# 08_BB_Processor.net
KiCad netlist of a schematic drawn in Altium Designer
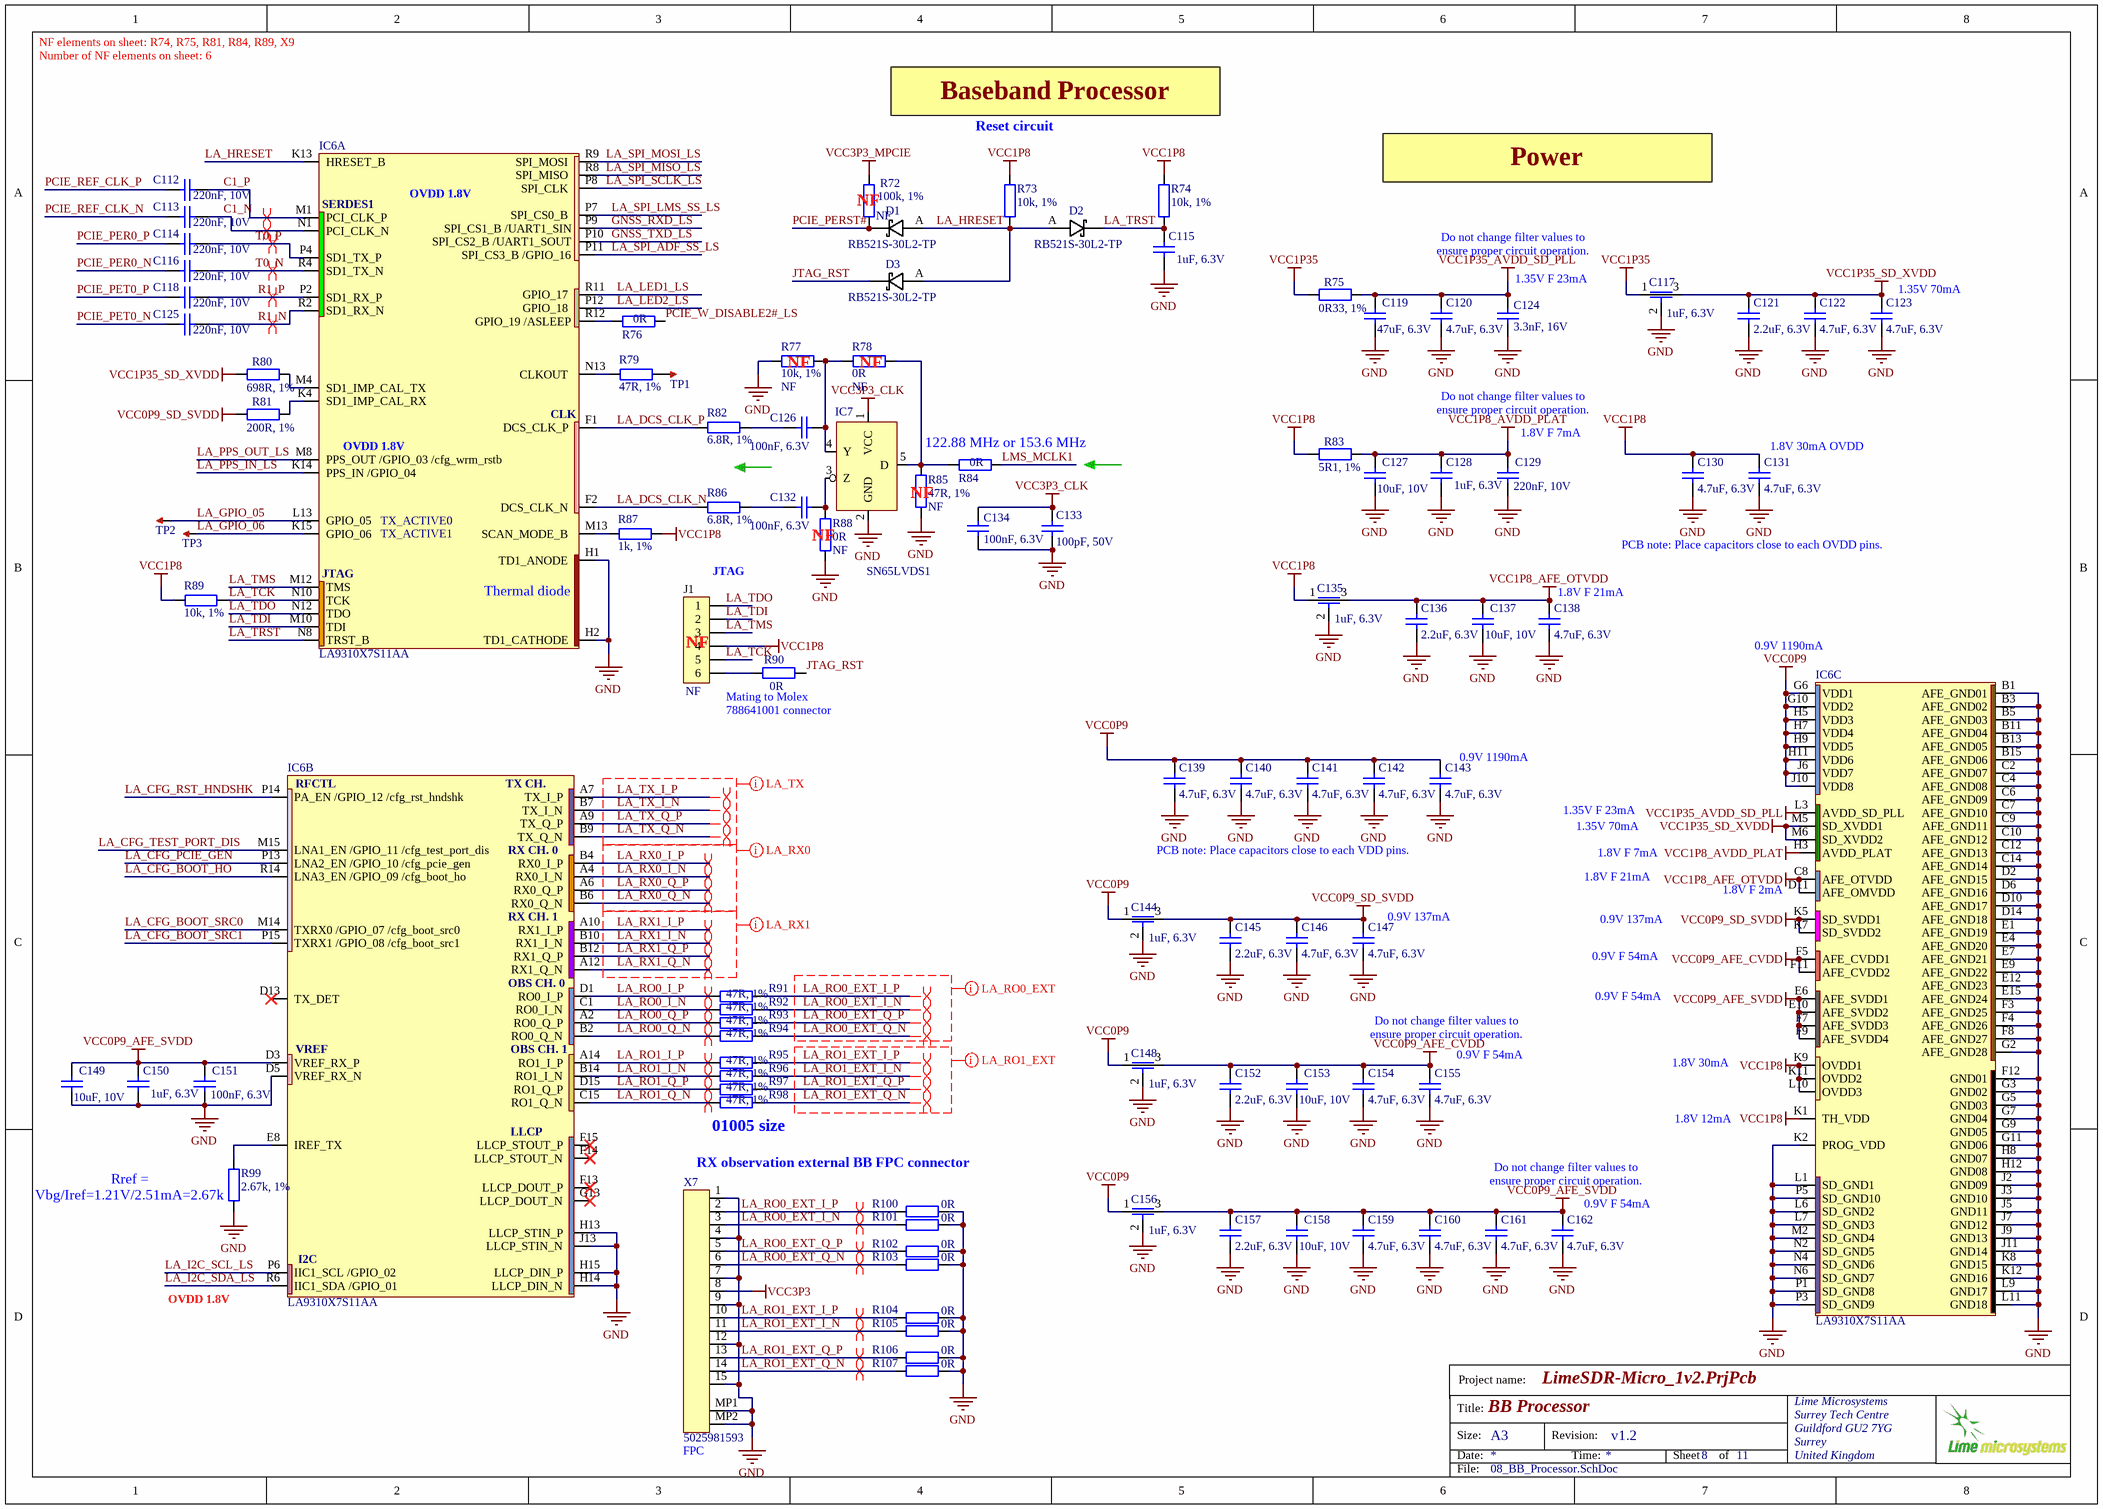
[diagram p0: 08_BB_Processor.SchDoc]

(export (version "E")
  (design (tool "Eeschema 10.0.6"))
  (components
    (comp (ref "C112")
      (value "220nF, 10V")
      (footprint "CAP0201")
      (fields
        (field (name "MANUFACTURER") "Murata")
        (field (name "TOLERANCE") "20%")
        (field (name "VOLTAGE") "10V")
      )
      (libsource (lib "LimeMicroAltiumLib_schLib") (part "Cap_0402"))
    )
    (comp (ref "C113")
      (value "220nF, 10V")
      (footprint "CAP0201")
      (fields
        (field (name "MANUFACTURER") "Murata")
        (field (name "TOLERANCE") "20%")
        (field (name "VOLTAGE") "10V")
      )
      (libsource (lib "LimeMicroAltiumLib_schLib") (part "Cap_0402"))
    )
    (comp (ref "C114")
      (value "220nF, 10V")
      (footprint "CAP0201")
      (fields
        (field (name "MANUFACTURER") "Murata")
        (field (name "TOLERANCE") "20%")
        (field (name "VOLTAGE") "10V")
      )
      (libsource (lib "LimeMicroAltiumLib_schLib") (part "Cap_0402"))
    )
    (comp (ref "C115")
      (value "1uF, 6.3V")
      (footprint "CAP0201")
      (fields (field (name "TOLERANCE") "±20%") (field (name "MANUFACTURER") "TDK Corporation"))
      (libsource (lib "LimeMicroAltiumLib_schLib") (part "Cap_0402"))
    )
    (comp (ref "C116")
      (value "220nF, 10V")
      (footprint "CAP0201")
      (fields
        (field (name "MANUFACTURER") "Murata")
        (field (name "TOLERANCE") "20%")
        (field (name "VOLTAGE") "10V")
      )
      (libsource (lib "LimeMicroAltiumLib_schLib") (part "Cap_0402"))
    )
    (comp (ref "C117")
      (value "1uF, 6.3V")
      (footprint "CAP0603_FEEDTHROUGH")
      (fields (field (name "MANUFACTURER") "TDK"))
      (libsource (lib "LimeMicroAltiumLib_schLib_r01") (part "Cap_feed_through"))
    )
    (comp (ref "C118")
      (value "220nF, 10V")
      (footprint "CAP0201")
      (fields
        (field (name "MANUFACTURER") "Murata")
        (field (name "TOLERANCE") "20%")
        (field (name "VOLTAGE") "10V")
      )
      (libsource (lib "LimeMicroAltiumLib_schLib") (part "Cap_0402"))
    )
    (comp (ref "C119")
      (value "47uF, 6.3V")
      (footprint "CAP0603")
      (fields (field (name "MANUFACTURER") "Murata") (field (name "TOLERANCE") "20%"))
      (libsource (lib "LimeFPGAboard_schLib") (part "Cap_0603"))
    )
    (comp (ref "C120")
      (value "4.7uF, 6.3V")
      (footprint "CAP0201")
      (fields (field (name "MANUFACTURER") "Murata") (field (name "TOLERANCE") "20%"))
      (libsource (lib "LimeMicroAltiumLib_schLib") (part "Cap_0402"))
    )
    (comp (ref "C121")
      (value "2.2uF, 6.3V")
      (footprint "CAP0201")
      (fields (field (name "MANUFACTURER") "Murata") (field (name "TOLERANCE") "20%"))
      (libsource (lib "LimeMicroAltiumLib_schLib") (part "Cap_0402"))
    )
    (comp (ref "C122")
      (value "4.7uF, 6.3V")
      (footprint "CAP0201")
      (fields (field (name "MANUFACTURER") "Murata") (field (name "TOLERANCE") "20%"))
      (libsource (lib "LimeMicroAltiumLib_schLib") (part "Cap_0402"))
    )
    (comp (ref "C123")
      (value "4.7uF, 6.3V")
      (footprint "CAP0201")
      (fields (field (name "MANUFACTURER") "Murata") (field (name "TOLERANCE") "20%"))
      (libsource (lib "LimeMicroAltiumLib_schLib") (part "Cap_0402"))
    )
    (comp (ref "C124")
      (value "3.3nF, 16V")
      (footprint "CAP0201")
      (fields (field (name "MANUFACTURER") "Murata"))
      (libsource (lib "LimeMicroAltiumLib_schLib") (part "Cap_0402"))
    )
    (comp (ref "C125")
      (value "220nF, 10V")
      (footprint "CAP0201")
      (fields
        (field (name "MANUFACTURER") "Murata")
        (field (name "TOLERANCE") "20%")
        (field (name "VOLTAGE") "10V")
      )
      (libsource (lib "LimeMicroAltiumLib_schLib") (part "Cap_0402"))
    )
    (comp (ref "C126")
      (value "100nF, 6.3V")
      (footprint "CAP0201")
      (fields (field (name "MANUFACTURER") "Samsung") (field (name "TOLERANCE") "20%"))
      (libsource (lib "LimeMicroAltiumLib_schLib") (part "Cap_0402"))
    )
    (comp (ref "C127")
      (value "10uF, 10V")
      (footprint "CAP0402")
      (fields (field (name "MANUFACTURER") "Murata"))
      (libsource (lib "LimeFPGAboard_schLib") (part "Cap_0603"))
    )
    (comp (ref "C128")
      (value "1uF, 6.3V")
      (footprint "CAP0201")
      (fields (field (name "TOLERANCE") "±20%") (field (name "MANUFACTURER") "TDK Corporation"))
      (libsource (lib "LimeMicroAltiumLib_schLib") (part "Cap_0402"))
    )
    (comp (ref "C129")
      (value "220nF, 10V")
      (footprint "CAP0201")
      (fields
        (field (name "MANUFACTURER") "Murata")
        (field (name "TOLERANCE") "20%")
        (field (name "VOLTAGE") "10V")
      )
      (libsource (lib "LimeMicroAltiumLib_schLib") (part "Cap_0402"))
    )
    (comp (ref "C130")
      (value "4.7uF, 6.3V")
      (footprint "CAP0201")
      (fields (field (name "MANUFACTURER") "Murata") (field (name "TOLERANCE") "20%"))
      (libsource (lib "LimeMicroAltiumLib_schLib") (part "Cap_0402"))
    )
    (comp (ref "C131")
      (value "4.7uF, 6.3V")
      (footprint "CAP0201")
      (fields (field (name "MANUFACTURER") "Murata") (field (name "TOLERANCE") "20%"))
      (libsource (lib "LimeMicroAltiumLib_schLib") (part "Cap_0402"))
    )
    (comp (ref "C132")
      (value "100nF, 6.3V")
      (footprint "CAP0201")
      (fields (field (name "MANUFACTURER") "Samsung") (field (name "TOLERANCE") "20%"))
      (libsource (lib "LimeMicroAltiumLib_schLib") (part "Cap_0402"))
    )
    (comp (ref "C133")
      (value "100pF, 50V")
      (footprint "CAP0201")
      (fields
        (field (name "MANUFACTURER") "TDK")
        (field (name "TOLERANCE") "5%")
        (field (name "VOLTAGE") "50V")
      )
      (libsource (lib "LimeMicroAltiumLib_schLib") (part "Cap_0402"))
    )
    (comp (ref "C134")
      (value "100nF, 6.3V")
      (footprint "CAP0201")
      (fields (field (name "MANUFACTURER") "Samsung") (field (name "TOLERANCE") "20%"))
      (libsource (lib "LimeMicroAltiumLib_schLib") (part "Cap_0402"))
    )
    (comp (ref "C135")
      (value "1uF, 6.3V")
      (footprint "CAP0603_FEEDTHROUGH")
      (fields (field (name "MANUFACTURER") "TDK"))
      (libsource (lib "LimeMicroAltiumLib_schLib_r01") (part "Cap_feed_through"))
    )
    (comp (ref "C136")
      (value "2.2uF, 6.3V")
      (footprint "CAP0201")
      (fields (field (name "MANUFACTURER") "Murata") (field (name "TOLERANCE") "20%"))
      (libsource (lib "LimeMicroAltiumLib_schLib") (part "Cap_0402"))
    )
    (comp (ref "C137")
      (value "10uF, 10V")
      (footprint "CAP0402")
      (fields (field (name "MANUFACTURER") "Murata"))
      (libsource (lib "LimeFPGAboard_schLib") (part "Cap_0603"))
    )
    (comp (ref "C138")
      (value "4.7uF, 6.3V")
      (footprint "CAP0201")
      (fields (field (name "MANUFACTURER") "Murata") (field (name "TOLERANCE") "20%"))
      (libsource (lib "LimeMicroAltiumLib_schLib") (part "Cap_0402"))
    )
    (comp (ref "C139")
      (value "4.7uF, 6.3V")
      (footprint "CAP0201")
      (fields (field (name "MANUFACTURER") "Murata") (field (name "TOLERANCE") "20%"))
      (libsource (lib "LimeMicroAltiumLib_schLib") (part "Cap_0402"))
    )
    (comp (ref "C140")
      (value "4.7uF, 6.3V")
      (footprint "CAP0201")
      (fields (field (name "MANUFACTURER") "Murata") (field (name "TOLERANCE") "20%"))
      (libsource (lib "LimeMicroAltiumLib_schLib") (part "Cap_0402"))
    )
    (comp (ref "C141")
      (value "4.7uF, 6.3V")
      (footprint "CAP0201")
      (fields (field (name "MANUFACTURER") "Murata") (field (name "TOLERANCE") "20%"))
      (libsource (lib "LimeMicroAltiumLib_schLib") (part "Cap_0402"))
    )
    (comp (ref "C142")
      (value "4.7uF, 6.3V")
      (footprint "CAP0201")
      (fields (field (name "MANUFACTURER") "Murata") (field (name "TOLERANCE") "20%"))
      (libsource (lib "LimeMicroAltiumLib_schLib") (part "Cap_0402"))
    )
    (comp (ref "C143")
      (value "4.7uF, 6.3V")
      (footprint "CAP0201")
      (fields (field (name "MANUFACTURER") "Murata") (field (name "TOLERANCE") "20%"))
      (libsource (lib "LimeMicroAltiumLib_schLib") (part "Cap_0402"))
    )
    (comp (ref "C144")
      (value "1uF, 6.3V")
      (footprint "CAP0603_FEEDTHROUGH")
      (fields (field (name "MANUFACTURER") "TDK"))
      (libsource (lib "LimeMicroAltiumLib_schLib_r01") (part "Cap_feed_through"))
    )
    (comp (ref "C145")
      (value "2.2uF, 6.3V")
      (footprint "CAP0201")
      (fields (field (name "MANUFACTURER") "Murata") (field (name "TOLERANCE") "20%"))
      (libsource (lib "LimeMicroAltiumLib_schLib") (part "Cap_0402"))
    )
    (comp (ref "C146")
      (value "4.7uF, 6.3V")
      (footprint "CAP0201")
      (fields (field (name "MANUFACTURER") "Murata") (field (name "TOLERANCE") "20%"))
      (libsource (lib "LimeMicroAltiumLib_schLib") (part "Cap_0402"))
    )
    (comp (ref "C147")
      (value "4.7uF, 6.3V")
      (footprint "CAP0201")
      (fields (field (name "MANUFACTURER") "Murata") (field (name "TOLERANCE") "20%"))
      (libsource (lib "LimeMicroAltiumLib_schLib") (part "Cap_0402"))
    )
    (comp (ref "C148")
      (value "1uF, 6.3V")
      (footprint "CAP0603_FEEDTHROUGH")
      (fields (field (name "MANUFACTURER") "TDK"))
      (libsource (lib "LimeMicroAltiumLib_schLib_r01") (part "Cap_feed_through"))
    )
    (comp (ref "C149")
      (value "10uF, 10V")
      (footprint "CAP0402")
      (fields (field (name "MANUFACTURER") "Murata"))
      (libsource (lib "LimeFPGAboard_schLib") (part "Cap_0603"))
    )
    (comp (ref "C150")
      (value "1uF, 6.3V")
      (footprint "CAP0201")
      (fields (field (name "TOLERANCE") "±20%") (field (name "MANUFACTURER") "TDK Corporation"))
      (libsource (lib "LimeMicroAltiumLib_schLib") (part "Cap_0402"))
    )
    (comp (ref "C151")
      (value "100nF, 6.3V")
      (footprint "CAP0201")
      (fields (field (name "MANUFACTURER") "Samsung") (field (name "TOLERANCE") "20%"))
      (libsource (lib "LimeMicroAltiumLib_schLib") (part "Cap_0402"))
    )
    (comp (ref "C152")
      (value "2.2uF, 6.3V")
      (footprint "CAP0201")
      (fields (field (name "MANUFACTURER") "Murata") (field (name "TOLERANCE") "20%"))
      (libsource (lib "LimeMicroAltiumLib_schLib") (part "Cap_0402"))
    )
    (comp (ref "C153")
      (value "10uF, 10V")
      (footprint "CAP0402")
      (fields (field (name "MANUFACTURER") "Murata"))
      (libsource (lib "LimeFPGAboard_schLib") (part "Cap_0603"))
    )
    (comp (ref "C154")
      (value "4.7uF, 6.3V")
      (footprint "CAP0201")
      (fields (field (name "MANUFACTURER") "Murata") (field (name "TOLERANCE") "20%"))
      (libsource (lib "LimeMicroAltiumLib_schLib") (part "Cap_0402"))
    )
    (comp (ref "C155")
      (value "4.7uF, 6.3V")
      (footprint "CAP0201")
      (fields (field (name "MANUFACTURER") "Murata") (field (name "TOLERANCE") "20%"))
      (libsource (lib "LimeMicroAltiumLib_schLib") (part "Cap_0402"))
    )
    (comp (ref "C156")
      (value "1uF, 6.3V")
      (footprint "CAP0603_FEEDTHROUGH")
      (fields (field (name "MANUFACTURER") "TDK"))
      (libsource (lib "LimeMicroAltiumLib_schLib_r01") (part "Cap_feed_through"))
    )
    (comp (ref "C157")
      (value "2.2uF, 6.3V")
      (footprint "CAP0201")
      (fields (field (name "MANUFACTURER") "Murata") (field (name "TOLERANCE") "20%"))
      (libsource (lib "LimeMicroAltiumLib_schLib") (part "Cap_0402"))
    )
    (comp (ref "C158")
      (value "10uF, 10V")
      (footprint "CAP0402")
      (fields (field (name "MANUFACTURER") "Murata"))
      (libsource (lib "LimeFPGAboard_schLib") (part "Cap_0603"))
    )
    (comp (ref "C159")
      (value "4.7uF, 6.3V")
      (footprint "CAP0201")
      (fields (field (name "MANUFACTURER") "Murata") (field (name "TOLERANCE") "20%"))
      (libsource (lib "LimeMicroAltiumLib_schLib") (part "Cap_0402"))
    )
    (comp (ref "C160")
      (value "4.7uF, 6.3V")
      (footprint "CAP0201")
      (fields (field (name "MANUFACTURER") "Murata") (field (name "TOLERANCE") "20%"))
      (libsource (lib "LimeMicroAltiumLib_schLib") (part "Cap_0402"))
    )
    (comp (ref "C161")
      (value "4.7uF, 6.3V")
      (footprint "CAP0201")
      (fields (field (name "MANUFACTURER") "Murata") (field (name "TOLERANCE") "20%"))
      (libsource (lib "LimeMicroAltiumLib_schLib") (part "Cap_0402"))
    )
    (comp (ref "C162")
      (value "4.7uF, 6.3V")
      (footprint "CAP0201")
      (fields (field (name "MANUFACTURER") "Murata") (field (name "TOLERANCE") "20%"))
      (libsource (lib "LimeMicroAltiumLib_schLib") (part "Cap_0402"))
    )
    (comp (ref "D1")
      (value "RB521S-30L2-TP")
      (footprint "RB521S-30L2-TP_DFN1006")
      (fields (field (name "MANUFACTURER") "MCC"))
      (libsource (lib "LimeMicroAltiumLib") (part "BAT46JFILM_shottky_diode"))
    )
    (comp (ref "D2")
      (value "RB521S-30L2-TP")
      (footprint "RB521S-30L2-TP_DFN1006")
      (fields (field (name "MANUFACTURER") "MCC"))
      (libsource (lib "LimeMicroAltiumLib") (part "BAT46JFILM_shottky_diode"))
    )
    (comp (ref "D3")
      (value "RB521S-30L2-TP")
      (footprint "RB521S-30L2-TP_DFN1006")
      (fields (field (name "MANUFACTURER") "MCC"))
      (libsource (lib "LimeMicroAltiumLib") (part "BAT46JFILM_shottky_diode"))
    )
    (comp (ref "IC6")
      (value "LA9310X7S11AA")
      (footprint "LA9310X7S11AA")
      (fields (field (name "MANUFACTURER") "NXP Semiconductors"))
      (libsource (lib "LimeMicroAltiumLib") (part "LA9310X7S11AA"))
    )
    (comp (ref "IC7")
      (value "SN65LVDS1")
      (footprint "SOT23-5_NO_SILK")
      (fields (field (name "MANUFACTURER") "TEXAS INSTRUMENTS"))
      (libsource (lib "LimeMicroAltiumLib_schLib") (part "SN65LVDS1"))
    )
    (comp (ref "J1")
      (value "Molex 0788641001")
      (footprint "Molex_0788641001_spring_contacts")
      (description "Header, 6-pin")
      (fields (field (name "MANUFACTURER") "Molex") (field (name "ASSEMBLY INFO") "NF"))
      (libsource (lib "LimeMicroAltiumLib_schLib_r04") (part "Molex_0788641001_spring_contacts"))
    )
    (comp (ref "R72")
      (value "100k, 1%")
      (footprint "RES0201")
      (fields
        (field (name "ASSEMBLY INFO") "NF")
        (field (name "MANUFACTURER") "Yageo")
        (field (name "TOLERANCE") "1%")
      )
      (libsource (lib "LimeFPGAboard_schLib") (part "Res_0402"))
    )
    (comp (ref "R73")
      (value "10k, 1%")
      (footprint "RES0201")
      (fields (field (name "MANUFACTURER") "Yageo") (field (name "TOLERANCE") "1%"))
      (libsource (lib "LimeFPGAboard_schLib") (part "Res_0402"))
    )
    (comp (ref "R74")
      (value "10k, 1%")
      (footprint "RES0201")
      (fields (field (name "MANUFACTURER") "Yageo") (field (name "TOLERANCE") "1%"))
      (libsource (lib "LimeFPGAboard_schLib") (part "Res_0402"))
    )
    (comp (ref "R75")
      (value "0R33, 1%")
      (footprint "RES0201")
      (fields (field (name "MANUFACTURER") "Ohmite"))
      (libsource (lib "LimeFPGAboard_schLib") (part "Res_0402"))
    )
    (comp (ref "R76")
      (value "0R")
      (footprint "RES0201")
      (fields (field (name "MANUFACTURER") "Yageo") (field (name "TOLERANCE") "5%"))
      (libsource (lib "LimeFPGAboard_schLib") (part "Res_0402"))
    )
    (comp (ref "R77")
      (value "10k, 1%")
      (footprint "RES0201")
      (fields
        (field (name "ASSEMBLY INFO") "NF")
        (field (name "MANUFACTURER") "Yageo")
        (field (name "TOLERANCE") "1%")
      )
      (libsource (lib "LimeFPGAboard_schLib") (part "Res_0402"))
    )
    (comp (ref "R78")
      (value "0R")
      (footprint "RES0201")
      (fields
        (field (name "ASSEMBLY INFO") "NF")
        (field (name "MANUFACTURER") "Yageo")
        (field (name "TOLERANCE") "5%")
      )
      (libsource (lib "LimeFPGAboard_schLib") (part "Res_0402"))
    )
    (comp (ref "R79")
      (value "47R, 1%")
      (footprint "RES0201")
      (fields (field (name "MANUFACTURER") "Yageo") (field (name "TOLERANCE") "1%"))
      (libsource (lib "LimeFPGAboard_schLib") (part "Res_0402"))
    )
    (comp (ref "R80")
      (value "698R, 1%")
      (footprint "RES0201")
      (fields (field (name "MANUFACTURER") "Yageo") (field (name "TOLERANCE") "1%"))
      (libsource (lib "LimeFPGAboard_schLib") (part "Res_0402"))
    )
    (comp (ref "R81")
      (value "200R, 1%")
      (footprint "RES0201")
      (fields (field (name "MANUFACTURER") "Yageo") (field (name "TOLERANCE") "1%"))
      (libsource (lib "LimeFPGAboard_schLib") (part "Res_0402"))
    )
    (comp (ref "R82")
      (value "6.8R, 1%")
      (footprint "RES0201")
      (fields (field (name "MANUFACTURER") "Yageo") (field (name "TOLERANCE") "1%"))
      (libsource (lib "LimeMicroAltiumLib_schLib") (part "Res_0402"))
    )
    (comp (ref "R83")
      (value "5R1, 1%")
      (footprint "RES0201")
      (fields (field (name "MANUFACTURER") "Yageo"))
      (libsource (lib "LimeFPGAboard_schLib") (part "Res_0402"))
    )
    (comp (ref "R84")
      (value "0R")
      (footprint "RES0201")
      (fields (field (name "MANUFACTURER") "Yageo") (field (name "TOLERANCE") "5%"))
      (libsource (lib "LimeFPGAboard_schLib") (part "Res_0402"))
    )
    (comp (ref "R85")
      (value "47R, 1%")
      (footprint "RES0201")
      (fields
        (field (name "ASSEMBLY INFO") "NF")
        (field (name "MANUFACTURER") "Yageo")
        (field (name "TOLERANCE") "1%")
      )
      (libsource (lib "LimeFPGAboard_schLib") (part "Res_0402"))
    )
    (comp (ref "R86")
      (value "6.8R, 1%")
      (footprint "RES0201")
      (fields (field (name "MANUFACTURER") "Yageo") (field (name "TOLERANCE") "1%"))
      (libsource (lib "LimeMicroAltiumLib_schLib") (part "Res_0402"))
    )
    (comp (ref "R87")
      (value "1k, 1%")
      (footprint "RES0201")
      (fields (field (name "MANUFACTURER") "Yageo") (field (name "TOLERANCE") "1%"))
      (libsource (lib "LimeMicroAltiumLib_schLib") (part "Res_0402"))
    )
    (comp (ref "R88")
      (value "0R")
      (footprint "RES0201")
      (fields
        (field (name "ASSEMBLY INFO") "NF")
        (field (name "MANUFACTURER") "Yageo")
        (field (name "TOLERANCE") "5%")
      )
      (libsource (lib "LimeFPGAboard_schLib") (part "Res_0402"))
    )
    (comp (ref "R89")
      (value "10k, 1%")
      (footprint "RES0201")
      (fields (field (name "MANUFACTURER") "Yageo") (field (name "TOLERANCE") "1%"))
      (libsource (lib "LimeFPGAboard_schLib") (part "Res_0402"))
    )
    (comp (ref "R90")
      (value "0R")
      (footprint "RES0201")
      (fields (field (name "MANUFACTURER") "Yageo") (field (name "TOLERANCE") "5%"))
      (libsource (lib "LimeFPGAboard_schLib") (part "Res_0402"))
    )
    (comp (ref "R91")
      (value "47R, 1%")
      (footprint "RES01005")
      (fields (field (name "MANUFACTURER") "Yageo") (field (name "TOLERANCE") "1%"))
      (libsource (lib "LimeFPGAboard_schLib") (part "Res_0402"))
    )
    (comp (ref "R92")
      (value "47R, 1%")
      (footprint "RES01005")
      (fields (field (name "MANUFACTURER") "Yageo") (field (name "TOLERANCE") "1%"))
      (libsource (lib "LimeFPGAboard_schLib") (part "Res_0402"))
    )
    (comp (ref "R93")
      (value "47R, 1%")
      (footprint "RES01005")
      (fields (field (name "MANUFACTURER") "Yageo") (field (name "TOLERANCE") "1%"))
      (libsource (lib "LimeFPGAboard_schLib") (part "Res_0402"))
    )
    (comp (ref "R94")
      (value "47R, 1%")
      (footprint "RES01005")
      (fields (field (name "MANUFACTURER") "Yageo") (field (name "TOLERANCE") "1%"))
      (libsource (lib "LimeFPGAboard_schLib") (part "Res_0402"))
    )
    (comp (ref "R95")
      (value "47R, 1%")
      (footprint "RES01005")
      (fields (field (name "MANUFACTURER") "Yageo") (field (name "TOLERANCE") "1%"))
      (libsource (lib "LimeFPGAboard_schLib") (part "Res_0402"))
    )
    (comp (ref "R96")
      (value "47R, 1%")
      (footprint "RES01005")
      (fields (field (name "MANUFACTURER") "Yageo") (field (name "TOLERANCE") "1%"))
      (libsource (lib "LimeFPGAboard_schLib") (part "Res_0402"))
    )
    (comp (ref "R97")
      (value "47R, 1%")
      (footprint "RES01005")
      (fields (field (name "MANUFACTURER") "Yageo") (field (name "TOLERANCE") "1%"))
      (libsource (lib "LimeFPGAboard_schLib") (part "Res_0402"))
    )
    (comp (ref "R98")
      (value "47R, 1%")
      (footprint "RES01005")
      (fields (field (name "MANUFACTURER") "Yageo") (field (name "TOLERANCE") "1%"))
      (libsource (lib "LimeFPGAboard_schLib") (part "Res_0402"))
    )
    (comp (ref "R99")
      (value "2.67k, 1%")
      (footprint "RES0201")
      (fields (field (name "MANUFACTURER") "Stackpole Electronics") (field (name "TOLERANCE") "1%"))
      (libsource (lib "LimeFPGAboard_schLib") (part "Res_0402"))
    )
    (comp (ref "R100")
      (value "0R")
      (footprint "RES01005")
      (fields (field (name "MANUFACTURER") "Panasonic") (field (name "TOLERANCE") "5%"))
      (libsource (lib "LimeFPGAboard_schLib") (part "Res_0402"))
    )
    (comp (ref "R101")
      (value "0R")
      (footprint "RES01005")
      (fields (field (name "MANUFACTURER") "Panasonic") (field (name "TOLERANCE") "5%"))
      (libsource (lib "LimeFPGAboard_schLib") (part "Res_0402"))
    )
    (comp (ref "R102")
      (value "0R")
      (footprint "RES01005")
      (fields (field (name "MANUFACTURER") "Panasonic") (field (name "TOLERANCE") "5%"))
      (libsource (lib "LimeFPGAboard_schLib") (part "Res_0402"))
    )
    (comp (ref "R103")
      (value "0R")
      (footprint "RES01005")
      (fields (field (name "MANUFACTURER") "Panasonic") (field (name "TOLERANCE") "5%"))
      (libsource (lib "LimeFPGAboard_schLib") (part "Res_0402"))
    )
    (comp (ref "R104")
      (value "0R")
      (footprint "RES01005")
      (fields (field (name "MANUFACTURER") "Panasonic") (field (name "TOLERANCE") "5%"))
      (libsource (lib "LimeFPGAboard_schLib") (part "Res_0402"))
    )
    (comp (ref "R105")
      (value "0R")
      (footprint "RES01005")
      (fields (field (name "MANUFACTURER") "Panasonic") (field (name "TOLERANCE") "5%"))
      (libsource (lib "LimeFPGAboard_schLib") (part "Res_0402"))
    )
    (comp (ref "R106")
      (value "0R")
      (footprint "RES01005")
      (fields (field (name "MANUFACTURER") "Panasonic") (field (name "TOLERANCE") "5%"))
      (libsource (lib "LimeFPGAboard_schLib") (part "Res_0402"))
    )
    (comp (ref "R107")
      (value "0R")
      (footprint "RES01005")
      (fields (field (name "MANUFACTURER") "Panasonic") (field (name "TOLERANCE") "5%"))
      (libsource (lib "LimeFPGAboard_schLib") (part "Res_0402"))
    )
    (comp (ref "TP1")
      (value "TESTPOINT_PAD")
      (footprint "TP_PAD_1MM")
      (description "Test Point PCB mount Miniature White")
      (libsource (lib "LimeMicroAltiumLib_schLib_r04") (part "TESTPOINT_PAD"))
    )
    (comp (ref "TP2")
      (value "TESTPOINT_PAD")
      (footprint "TP_PAD_1MM")
      (description "Test Point PCB mount Miniature White")
      (libsource (lib "LimeMicroAltiumLib_schLib_r04") (part "TESTPOINT_PAD"))
    )
    (comp (ref "TP3")
      (value "TESTPOINT_PAD")
      (footprint "TP_PAD_1MM")
      (description "Test Point PCB mount Miniature White")
      (libsource (lib "LimeMicroAltiumLib_schLib_r04") (part "TESTPOINT_PAD"))
    )
    (comp (ref "X7")
      (value "5025981593")
      (footprint "5025981593_FPC_connector")
      (fields (field (name "MANUFACTURER") "Molex"))
      (libsource (lib "LimeMicroAltiumLib_schLib_r04") (part "5025981593_FPC_connector"))
    )
  )
  (nets
    (net (code "1") (name "/C1_N") (class "Default")
      (node (ref "C113") (pin "2") (pinfunction "2_2") (pintype "passive"))
      (node (ref "IC6") (pin "N1") (pinfunction "PCI_CLK_N_N1") (pintype "power_in"))
    )
    (net (code "2") (name "/C1_P") (class "Default")
      (node (ref "C112") (pin "2") (pinfunction "2_2") (pintype "passive"))
      (node (ref "IC6") (pin "M1") (pinfunction "PCI_CLK_P_M1") (pintype "power_in"))
    )
    (net (code "3") (name "/GNSS_RXD_LS") (class "Default")
      (node (ref "IC6") (pin "P9") (pinfunction "SPI_CS1_B_/UART1_SIN_P9") (pintype "power_in"))
    )
    (net (code "4") (name "/GNSS_TXD_LS") (class "Default")
      (node (ref "IC6") (pin "P10") (pinfunction "SPI_CS2_B_/UART1_SOUT_P10") (pintype "power_in"))
    )
    (net (code "5") (name "/JTAG_RST") (class "Default")
      (node (ref "D3") (pin "C") (pinfunction "C_C") (pintype "passive"))
      (node (ref "R90") (pin "2") (pinfunction "2_2") (pintype "passive"))
    )
    (net (code "6") (name "/LA_CFG_BOOT_HO") (class "Default")
      (node (ref "IC6") (pin "R14") (pinfunction "LNA3_EN_/GPIO_09_/cfg_boot_ho_R14") (pintype "power_in"))
    )
    (net (code "7") (name "/LA_CFG_BOOT_SRC0") (class "Default")
      (node (ref "IC6") (pin "M14") (pinfunction "TXRX0_/GPIO_07_/cfg_boot_src0_M14") (pintype "power_in"))
    )
    (net (code "8") (name "/LA_CFG_BOOT_SRC1") (class "Default")
      (node (ref "IC6") (pin "P15") (pinfunction "TXRX1_/GPIO_08_/cfg_boot_src1_P15") (pintype "power_in"))
    )
    (net (code "9") (name "/LA_CFG_PCIE_GEN") (class "Default")
      (node (ref "IC6") (pin "P13") (pinfunction "LNA2_EN_/GPIO_10_/cfg_pcie_gen_P13") (pintype "power_in"))
    )
    (net (code "10") (name "/LA_CFG_RST_HNDSHK") (class "Default")
      (node (ref "IC6") (pin "P14") (pinfunction "PA_EN_/GPIO_12_/cfg_rst_hndshk_P14") (pintype "power_in"))
    )
    (net (code "11") (name "/LA_CFG_TEST_PORT_DIS") (class "Default")
      (node (ref "IC6") (pin "M15") (pinfunction "LNA1_EN_/GPIO_11_/cfg_test_port_dis_M15") (pintype "power_in"))
    )
    (net (code "12") (name "/LA_DCS_CLK_N") (class "Default")
      (node (ref "IC6") (pin "F2") (pinfunction "DCS_CLK_N_F2") (pintype "power_in"))
      (node (ref "R86") (pin "2") (pinfunction "2_2") (pintype "passive"))
    )
    (net (code "13") (name "/LA_DCS_CLK_P") (class "Default")
      (node (ref "IC6") (pin "F1") (pinfunction "DCS_CLK_P_F1") (pintype "power_in"))
      (node (ref "R82") (pin "2") (pinfunction "2_2") (pintype "passive"))
    )
    (net (code "14") (name "/LA_GPIO_05") (class "Default")
      (node (ref "IC6") (pin "L13") (pinfunction "GPIO_05_L13") (pintype "power_in"))
      (node (ref "TP2") (pin "1") (pintype "passive"))
    )
    (net (code "15") (name "/LA_GPIO_06") (class "Default")
      (node (ref "IC6") (pin "K15") (pinfunction "GPIO_06_K15") (pintype "power_in"))
      (node (ref "TP3") (pin "1") (pintype "passive"))
    )
    (net (code "16") (name "/LA_HRESET") (class "Default")
      (node (ref "D1") (pin "A") (pinfunction "A_A") (pintype "passive"))
      (node (ref "D2") (pin "A") (pinfunction "A_A") (pintype "passive"))
      (node (ref "D3") (pin "A") (pinfunction "A_A") (pintype "passive"))
      (node (ref "IC6") (pin "K13") (pinfunction "HRESET_B_K13") (pintype "power_in"))
      (node (ref "R73") (pin "2") (pinfunction "2_2") (pintype "passive"))
    )
    (net (code "17") (name "/LA_I2C_SCL_LS") (class "Default")
      (node (ref "IC6") (pin "P6") (pinfunction "IIC1_SCL_/GPIO_02_P6") (pintype "power_in"))
    )
    (net (code "18") (name "/LA_I2C_SDA_LS") (class "Default")
      (node (ref "IC6") (pin "R6") (pinfunction "IIC1_SDA_/GPIO_01_R6") (pintype "power_in"))
    )
    (net (code "19") (name "/LA_LED1_LS") (class "Default")
      (node (ref "IC6") (pin "R11") (pinfunction "GPIO_17_R11") (pintype "power_in"))
    )
    (net (code "20") (name "/LA_LED2_LS") (class "Default")
      (node (ref "IC6") (pin "P12") (pinfunction "GPIO_18_P12") (pintype "power_in"))
    )
    (net (code "21") (name "/LA_PPS_IN_LS") (class "Default")
      (node (ref "IC6") (pin "K14") (pinfunction "PPS_IN_/GPIO_04_K14") (pintype "power_in"))
    )
    (net (code "22") (name "/LA_PPS_OUT_LS") (class "Default")
      (node (ref "IC6") (pin "M8") (pinfunction "PPS_OUT_/GPIO_03_/cfg_wrm_rstb_M8") (pintype "power_in"))
    )
    (net (code "23") (name "/LA_RO0_EXT_I_N") (class "Default")
      (node (ref "R101") (pin "1") (pinfunction "1_1") (pintype "passive"))
      (node (ref "R92") (pin "2") (pinfunction "2_2") (pintype "passive"))
      (node (ref "X7") (pin "3") (pinfunction "3_3") (pintype "passive"))
    )
    (net (code "24") (name "/LA_RO0_EXT_I_P") (class "Default")
      (node (ref "R100") (pin "1") (pinfunction "1_1") (pintype "passive"))
      (node (ref "R91") (pin "2") (pinfunction "2_2") (pintype "passive"))
      (node (ref "X7") (pin "2") (pinfunction "2_2") (pintype "passive"))
    )
    (net (code "25") (name "/LA_RO0_EXT_Q_N") (class "Default")
      (node (ref "R103") (pin "1") (pinfunction "1_1") (pintype "passive"))
      (node (ref "R94") (pin "2") (pinfunction "2_2") (pintype "passive"))
      (node (ref "X7") (pin "6") (pinfunction "6_6") (pintype "passive"))
    )
    (net (code "26") (name "/LA_RO0_EXT_Q_P") (class "Default")
      (node (ref "R102") (pin "1") (pinfunction "1_1") (pintype "passive"))
      (node (ref "R93") (pin "2") (pinfunction "2_2") (pintype "passive"))
      (node (ref "X7") (pin "5") (pinfunction "5_5") (pintype "passive"))
    )
    (net (code "27") (name "/LA_RO0_I_N") (class "Default")
      (node (ref "IC6") (pin "C1") (pinfunction "RO0_I_N_C1") (pintype "power_in"))
      (node (ref "R92") (pin "1") (pinfunction "1_1") (pintype "passive"))
    )
    (net (code "28") (name "/LA_RO0_I_P") (class "Default")
      (node (ref "IC6") (pin "D1") (pinfunction "RO0_I_P_D1") (pintype "power_in"))
      (node (ref "R91") (pin "1") (pinfunction "1_1") (pintype "passive"))
    )
    (net (code "29") (name "/LA_RO0_Q_N") (class "Default")
      (node (ref "IC6") (pin "B2") (pinfunction "RO0_Q_N_B2") (pintype "power_in"))
      (node (ref "R94") (pin "1") (pinfunction "1_1") (pintype "passive"))
    )
    (net (code "30") (name "/LA_RO0_Q_P") (class "Default")
      (node (ref "IC6") (pin "A2") (pinfunction "RO0_Q_P_A2") (pintype "power_in"))
      (node (ref "R93") (pin "1") (pinfunction "1_1") (pintype "passive"))
    )
    (net (code "31") (name "/LA_RO1_EXT_I_N") (class "Default")
      (node (ref "R105") (pin "1") (pinfunction "1_1") (pintype "passive"))
      (node (ref "R96") (pin "2") (pinfunction "2_2") (pintype "passive"))
      (node (ref "X7") (pin "11") (pinfunction "11_11") (pintype "passive"))
    )
    (net (code "32") (name "/LA_RO1_EXT_I_P") (class "Default")
      (node (ref "R104") (pin "1") (pinfunction "1_1") (pintype "passive"))
      (node (ref "R95") (pin "2") (pinfunction "2_2") (pintype "passive"))
      (node (ref "X7") (pin "10") (pinfunction "10_10") (pintype "passive"))
    )
    (net (code "33") (name "/LA_RO1_EXT_Q_N") (class "Default")
      (node (ref "R107") (pin "1") (pinfunction "1_1") (pintype "passive"))
      (node (ref "R98") (pin "2") (pinfunction "2_2") (pintype "passive"))
      (node (ref "X7") (pin "14") (pinfunction "14_14") (pintype "passive"))
    )
    (net (code "34") (name "/LA_RO1_EXT_Q_P") (class "Default")
      (node (ref "R106") (pin "1") (pinfunction "1_1") (pintype "passive"))
      (node (ref "R97") (pin "2") (pinfunction "2_2") (pintype "passive"))
      (node (ref "X7") (pin "13") (pinfunction "13_13") (pintype "passive"))
    )
    (net (code "35") (name "/LA_RO1_I_N") (class "Default")
      (node (ref "IC6") (pin "B14") (pinfunction "RO1_I_N_B14") (pintype "power_in"))
      (node (ref "R96") (pin "1") (pinfunction "1_1") (pintype "passive"))
    )
    (net (code "36") (name "/LA_RO1_I_P") (class "Default")
      (node (ref "IC6") (pin "A14") (pinfunction "RO1_I_P_A14") (pintype "power_in"))
      (node (ref "R95") (pin "1") (pinfunction "1_1") (pintype "passive"))
    )
    (net (code "37") (name "/LA_RO1_Q_N") (class "Default")
      (node (ref "IC6") (pin "C15") (pinfunction "RO1_Q_N_C15") (pintype "power_in"))
      (node (ref "R98") (pin "1") (pinfunction "1_1") (pintype "passive"))
    )
    (net (code "38") (name "/LA_RO1_Q_P") (class "Default")
      (node (ref "IC6") (pin "D15") (pinfunction "RO1_Q_P_D15") (pintype "power_in"))
      (node (ref "R97") (pin "1") (pinfunction "1_1") (pintype "passive"))
    )
    (net (code "39") (name "/LA_RX0_I_N") (class "Default")
      (node (ref "IC6") (pin "A4") (pinfunction "RX0_I_N_A4") (pintype "power_in"))
    )
    (net (code "40") (name "/LA_RX0_I_P") (class "Default")
      (node (ref "IC6") (pin "B4") (pinfunction "RX0_I_P_B4") (pintype "power_in"))
    )
    (net (code "41") (name "/LA_RX0_Q_N") (class "Default")
      (node (ref "IC6") (pin "B6") (pinfunction "RX0_Q_N_B6") (pintype "power_in"))
    )
    (net (code "42") (name "/LA_RX0_Q_P") (class "Default")
      (node (ref "IC6") (pin "A6") (pinfunction "RX0_Q_P_A6") (pintype "power_in"))
    )
    (net (code "43") (name "/LA_RX1_I_N") (class "Default")
      (node (ref "IC6") (pin "B10") (pinfunction "RX1_I_N_B10") (pintype "power_in"))
    )
    (net (code "44") (name "/LA_RX1_I_P") (class "Default")
      (node (ref "IC6") (pin "A10") (pinfunction "RX1_I_P_A10") (pintype "power_in"))
    )
    (net (code "45") (name "/LA_RX1_Q_N") (class "Default")
      (node (ref "IC6") (pin "A12") (pinfunction "RX1_Q_N_A12") (pintype "power_in"))
    )
    (net (code "46") (name "/LA_RX1_Q_P") (class "Default")
      (node (ref "IC6") (pin "B12") (pinfunction "RX1_Q_P_B12") (pintype "power_in"))
    )
    (net (code "47") (name "/LA_SPI_ADF_SS_LS") (class "Default")
      (node (ref "IC6") (pin "P11") (pinfunction "SPI_CS3_B_/GPIO_16_P11") (pintype "power_in"))
    )
    (net (code "48") (name "/LA_SPI_LMS_SS_LS") (class "Default")
      (node (ref "IC6") (pin "P7") (pinfunction "SPI_CS0_B_P7") (pintype "power_in"))
    )
    (net (code "49") (name "/LA_SPI_MISO_LS") (class "Default")
      (node (ref "IC6") (pin "R8") (pinfunction "SPI_MISO_R8") (pintype "power_in"))
    )
    (net (code "50") (name "/LA_SPI_MOSI_LS") (class "Default")
      (node (ref "IC6") (pin "R9") (pinfunction "SPI_MOSI_R9") (pintype "power_in"))
    )
    (net (code "51") (name "/LA_SPI_SCLK_LS") (class "Default")
      (node (ref "IC6") (pin "P8") (pinfunction "SPI_CLK_P8") (pintype "power_in"))
    )
    (net (code "52") (name "/LA_TCK") (class "Default")
      (node (ref "IC6") (pin "N10") (pinfunction "TCK_N10") (pintype "power_in"))
      (node (ref "J1") (pin "5") (pinfunction "5_5") (pintype "passive"))
      (node (ref "R89") (pin "2") (pinfunction "2_2") (pintype "passive"))
    )
    (net (code "53") (name "/LA_TDI") (class "Default")
      (node (ref "IC6") (pin "M10") (pinfunction "TDI_M10") (pintype "power_in"))
      (node (ref "J1") (pin "2") (pinfunction "2_2") (pintype "passive"))
    )
    (net (code "54") (name "/LA_TDO") (class "Default")
      (node (ref "IC6") (pin "N12") (pinfunction "TDO_N12") (pintype "power_in"))
      (node (ref "J1") (pin "1") (pinfunction "1_1") (pintype "passive"))
    )
    (net (code "55") (name "/LA_TMS") (class "Default")
      (node (ref "IC6") (pin "M12") (pinfunction "TMS_M12") (pintype "power_in"))
      (node (ref "J1") (pin "3") (pinfunction "3_3") (pintype "passive"))
    )
    (net (code "56") (name "/LA_TRST") (class "Default")
      (node (ref "C115") (pin "1") (pinfunction "1_1") (pintype "passive"))
      (node (ref "D2") (pin "C") (pinfunction "C_C") (pintype "passive"))
      (node (ref "IC6") (pin "N8") (pinfunction "TRST_B_N8") (pintype "power_in"))
      (node (ref "R74") (pin "2") (pinfunction "2_2") (pintype "passive"))
    )
    (net (code "57") (name "/LA_TX_I_N") (class "Default")
      (node (ref "IC6") (pin "B7") (pinfunction "TX_I_N_B7") (pintype "power_in"))
    )
    (net (code "58") (name "/LA_TX_I_P") (class "Default")
      (node (ref "IC6") (pin "A7") (pinfunction "TX_I_P_A7") (pintype "power_in"))
    )
    (net (code "59") (name "/LA_TX_Q_N") (class "Default")
      (node (ref "IC6") (pin "B9") (pinfunction "TX_Q_N_B9") (pintype "power_in"))
    )
    (net (code "60") (name "/LA_TX_Q_P") (class "Default")
      (node (ref "IC6") (pin "A9") (pinfunction "TX_Q_P_A9") (pintype "power_in"))
    )
    (net (code "61") (name "/LMS_MCLK1") (class "Default")
      (node (ref "R84") (pin "1") (pinfunction "1_1") (pintype "passive"))
    )
    (net (code "62") (name "/PCIE_PER0_N") (class "Default")
      (node (ref "C116") (pin "1") (pinfunction "1_1") (pintype "passive"))
    )
    (net (code "63") (name "/PCIE_PER0_P") (class "Default")
      (node (ref "C114") (pin "1") (pinfunction "1_1") (pintype "passive"))
    )
    (net (code "64") (name "/PCIE_PERST#") (class "Default")
      (node (ref "D1") (pin "C") (pinfunction "C_C") (pintype "passive"))
      (node (ref "R72") (pin "2") (pinfunction "2_2") (pintype "passive"))
    )
    (net (code "65") (name "/PCIE_PET0_N") (class "Default")
      (node (ref "C125") (pin "1") (pinfunction "1_1") (pintype "passive"))
    )
    (net (code "66") (name "/PCIE_PET0_P") (class "Default")
      (node (ref "C118") (pin "1") (pinfunction "1_1") (pintype "passive"))
    )
    (net (code "67") (name "/PCIE_REF_CLK_N") (class "Default")
      (node (ref "C113") (pin "1") (pinfunction "1_1") (pintype "passive"))
    )
    (net (code "68") (name "/PCIE_REF_CLK_P") (class "Default")
      (node (ref "C112") (pin "1") (pinfunction "1_1") (pintype "passive"))
    )
    (net (code "69") (name "/PCIE_W_DISABLE2#_LS") (class "Default")
      (node (ref "R76") (pin "1") (pinfunction "1_1") (pintype "passive"))
    )
    (net (code "70") (name "/R1_N") (class "Default")
      (node (ref "C125") (pin "2") (pinfunction "2_2") (pintype "passive"))
      (node (ref "IC6") (pin "R2") (pinfunction "SD1_RX_N_R2") (pintype "power_in"))
    )
    (net (code "71") (name "/R1_P") (class "Default")
      (node (ref "C118") (pin "2") (pinfunction "2_2") (pintype "passive"))
      (node (ref "IC6") (pin "P2") (pinfunction "SD1_RX_P_P2") (pintype "power_in"))
    )
    (net (code "72") (name "/T0_N") (class "Default")
      (node (ref "C116") (pin "2") (pinfunction "2_2") (pintype "passive"))
      (node (ref "IC6") (pin "R4") (pinfunction "SD1_TX_N_R4") (pintype "power_in"))
    )
    (net (code "73") (name "/T0_P") (class "Default")
      (node (ref "C114") (pin "2") (pinfunction "2_2") (pintype "passive"))
      (node (ref "IC6") (pin "P4") (pinfunction "SD1_TX_P_P4") (pintype "power_in"))
    )
    (net (code "74") (name "GND") (class "Default")
      (node (ref "C115") (pin "2") (pinfunction "2_2") (pintype "passive"))
      (node (ref "C117") (pin "2") (pinfunction "2_2") (pintype "passive"))
      (node (ref "C119") (pin "1") (pinfunction "1_1") (pintype "passive"))
      (node (ref "C120") (pin "1") (pinfunction "1_1") (pintype "passive"))
      (node (ref "C121") (pin "1") (pinfunction "1_1") (pintype "passive"))
      (node (ref "C122") (pin "1") (pinfunction "1_1") (pintype "passive"))
      (node (ref "C123") (pin "1") (pinfunction "1_1") (pintype "passive"))
      (node (ref "C124") (pin "2") (pinfunction "2_2") (pintype "passive"))
      (node (ref "C127") (pin "1") (pinfunction "1_1") (pintype "passive"))
      (node (ref "C128") (pin "2") (pinfunction "2_2") (pintype "passive"))
      (node (ref "C129") (pin "2") (pinfunction "2_2") (pintype "passive"))
      (node (ref "C130") (pin "1") (pinfunction "1_1") (pintype "passive"))
      (node (ref "C131") (pin "1") (pinfunction "1_1") (pintype "passive"))
      (node (ref "C133") (pin "1") (pinfunction "1_1") (pintype "passive"))
      (node (ref "C134") (pin "2") (pinfunction "2_2") (pintype "passive"))
      (node (ref "C135") (pin "2") (pinfunction "2_2") (pintype "passive"))
      (node (ref "C136") (pin "1") (pinfunction "1_1") (pintype "passive"))
      (node (ref "C137") (pin "1") (pinfunction "1_1") (pintype "passive"))
      (node (ref "C138") (pin "1") (pinfunction "1_1") (pintype "passive"))
      (node (ref "C139") (pin "1") (pinfunction "1_1") (pintype "passive"))
      (node (ref "C140") (pin "1") (pinfunction "1_1") (pintype "passive"))
      (node (ref "C141") (pin "1") (pinfunction "1_1") (pintype "passive"))
      (node (ref "C142") (pin "1") (pinfunction "1_1") (pintype "passive"))
      (node (ref "C143") (pin "1") (pinfunction "1_1") (pintype "passive"))
      (node (ref "C144") (pin "2") (pinfunction "2_2") (pintype "passive"))
      (node (ref "C145") (pin "1") (pinfunction "1_1") (pintype "passive"))
      (node (ref "C146") (pin "1") (pinfunction "1_1") (pintype "passive"))
      (node (ref "C147") (pin "1") (pinfunction "1_1") (pintype "passive"))
      (node (ref "C148") (pin "2") (pinfunction "2_2") (pintype "passive"))
      (node (ref "C149") (pin "1") (pinfunction "1_1") (pintype "passive"))
      (node (ref "C150") (pin "2") (pinfunction "2_2") (pintype "passive"))
      (node (ref "C151") (pin "2") (pinfunction "2_2") (pintype "passive"))
      (node (ref "C152") (pin "1") (pinfunction "1_1") (pintype "passive"))
      (node (ref "C153") (pin "1") (pinfunction "1_1") (pintype "passive"))
      (node (ref "C154") (pin "1") (pinfunction "1_1") (pintype "passive"))
      (node (ref "C155") (pin "1") (pinfunction "1_1") (pintype "passive"))
      (node (ref "C156") (pin "2") (pinfunction "2_2") (pintype "passive"))
      (node (ref "C157") (pin "1") (pinfunction "1_1") (pintype "passive"))
      (node (ref "C158") (pin "1") (pinfunction "1_1") (pintype "passive"))
      (node (ref "C159") (pin "1") (pinfunction "1_1") (pintype "passive"))
      (node (ref "C160") (pin "1") (pinfunction "1_1") (pintype "passive"))
      (node (ref "C161") (pin "1") (pinfunction "1_1") (pintype "passive"))
      (node (ref "C162") (pin "1") (pinfunction "1_1") (pintype "passive"))
      (node (ref "IC6") (pin "B1") (pinfunction "AFE_GND01_B1") (pintype "power_in"))
      (node (ref "IC6") (pin "B11") (pinfunction "AFE_GND04_B11") (pintype "power_in"))
      (node (ref "IC6") (pin "B13") (pinfunction "AFE_GND05_B13") (pintype "power_in"))
      (node (ref "IC6") (pin "B15") (pinfunction "AFE_GND06_B15") (pintype "power_in"))
      (node (ref "IC6") (pin "B3") (pinfunction "AFE_GND02_B3") (pintype "power_in"))
      (node (ref "IC6") (pin "B5") (pinfunction "AFE_GND03_B5") (pintype "power_in"))
      (node (ref "IC6") (pin "C10") (pinfunction "AFE_GND12_C10") (pintype "power_in"))
      (node (ref "IC6") (pin "C12") (pinfunction "AFE_GND13_C12") (pintype "power_in"))
      (node (ref "IC6") (pin "C14") (pinfunction "AFE_GND14_C14") (pintype "power_in"))
      (node (ref "IC6") (pin "C2") (pinfunction "AFE_GND07_C2") (pintype "power_in"))
      (node (ref "IC6") (pin "C4") (pinfunction "AFE_GND08_C4") (pintype "power_in"))
      (node (ref "IC6") (pin "C6") (pinfunction "AFE_GND09_C6") (pintype "power_in"))
      (node (ref "IC6") (pin "C7") (pinfunction "AFE_GND10_C7") (pintype "power_in"))
      (node (ref "IC6") (pin "C9") (pinfunction "AFE_GND11_C9") (pintype "power_in"))
      (node (ref "IC6") (pin "D10") (pinfunction "AFE_GND17_D10") (pintype "power_in"))
      (node (ref "IC6") (pin "D14") (pinfunction "AFE_GND18_D14") (pintype "power_in"))
      (node (ref "IC6") (pin "D2") (pinfunction "AFE_GND15_D2") (pintype "power_in"))
      (node (ref "IC6") (pin "D5") (pinfunction "VREF_RX_N_D5") (pintype "power_in"))
      (node (ref "IC6") (pin "D6") (pinfunction "AFE_GND16_D6") (pintype "power_in"))
      (node (ref "IC6") (pin "E1") (pinfunction "AFE_GND19_E1") (pintype "power_in"))
      (node (ref "IC6") (pin "E12") (pinfunction "AFE_GND23_E12") (pintype "power_in"))
      (node (ref "IC6") (pin "E15") (pinfunction "AFE_GND24_E15") (pintype "power_in"))
      (node (ref "IC6") (pin "E4") (pinfunction "AFE_GND20_E4") (pintype "power_in"))
      (node (ref "IC6") (pin "E7") (pinfunction "AFE_GND21_E7") (pintype "power_in"))
      (node (ref "IC6") (pin "E9") (pinfunction "AFE_GND22_E9") (pintype "power_in"))
      (node (ref "IC6") (pin "F12") (pinfunction "GND01_F12") (pintype "power_in"))
      (node (ref "IC6") (pin "F3") (pinfunction "AFE_GND25_F3") (pintype "power_in"))
      (node (ref "IC6") (pin "F4") (pinfunction "AFE_GND26_F4") (pintype "power_in"))
      (node (ref "IC6") (pin "F8") (pinfunction "AFE_GND27_F8") (pintype "power_in"))
      (node (ref "IC6") (pin "G11") (pinfunction "GND06_G11") (pintype "power_in"))
      (node (ref "IC6") (pin "G2") (pinfunction "AFE_GND28_G2") (pintype "power_in"))
      (node (ref "IC6") (pin "G3") (pinfunction "GND02_G3") (pintype "power_in"))
      (node (ref "IC6") (pin "G5") (pinfunction "GND03_G5") (pintype "power_in"))
      (node (ref "IC6") (pin "G7") (pinfunction "GND04_G7") (pintype "power_in"))
      (node (ref "IC6") (pin "G9") (pinfunction "GND05_G9") (pintype "power_in"))
      (node (ref "IC6") (pin "H1") (pinfunction "TD1_ANODE_H1") (pintype "power_in"))
      (node (ref "IC6") (pin "H12") (pinfunction "GND08_H12") (pintype "power_in"))
      (node (ref "IC6") (pin "H13") (pinfunction "LLCP_STIN_P_H13") (pintype "power_in"))
      (node (ref "IC6") (pin "H14") (pinfunction "LLCP_DIN_N_H14") (pintype "power_in"))
      (node (ref "IC6") (pin "H15") (pinfunction "LLCP_DIN_P_H15") (pintype "power_in"))
      (node (ref "IC6") (pin "H2") (pinfunction "TD1_CATHODE_H2") (pintype "power_in"))
      (node (ref "IC6") (pin "H8") (pinfunction "GND07_H8") (pintype "power_in"))
      (node (ref "IC6") (pin "J11") (pinfunction "GND14_J11") (pintype "power_in"))
      (node (ref "IC6") (pin "J13") (pinfunction "LLCP_STIN_N_J13") (pintype "power_in"))
      (node (ref "IC6") (pin "J2") (pinfunction "GND09_J2") (pintype "power_in"))
      (node (ref "IC6") (pin "J3") (pinfunction "GND10_J3") (pintype "power_in"))
      (node (ref "IC6") (pin "J5") (pinfunction "GND11_J5") (pintype "power_in"))
      (node (ref "IC6") (pin "J7") (pinfunction "GND12_J7") (pintype "power_in"))
      (node (ref "IC6") (pin "J9") (pinfunction "GND13_J9") (pintype "power_in"))
      (node (ref "IC6") (pin "K12") (pinfunction "GND16_K12") (pintype "power_in"))
      (node (ref "IC6") (pin "K2") (pinfunction "PROG_VDD_K2") (pintype "power_in"))
      (node (ref "IC6") (pin "K8") (pinfunction "GND15_K8") (pintype "power_in"))
      (node (ref "IC6") (pin "L1") (pinfunction "SD_GND1_L1") (pintype "power_in"))
      (node (ref "IC6") (pin "L11") (pinfunction "GND18_L11") (pintype "power_in"))
      (node (ref "IC6") (pin "L6") (pinfunction "SD_GND2_L6") (pintype "power_in"))
      (node (ref "IC6") (pin "L7") (pinfunction "SD_GND3_L7") (pintype "power_in"))
      (node (ref "IC6") (pin "L9") (pinfunction "GND17_L9") (pintype "power_in"))
      (node (ref "IC6") (pin "M2") (pinfunction "SD_GND4_M2") (pintype "power_in"))
      (node (ref "IC6") (pin "N2") (pinfunction "SD_GND5_N2") (pintype "power_in"))
      (node (ref "IC6") (pin "N4") (pinfunction "SD_GND6_N4") (pintype "power_in"))
      (node (ref "IC6") (pin "N6") (pinfunction "SD_GND7_N6") (pintype "power_in"))
      (node (ref "IC6") (pin "P1") (pinfunction "SD_GND8_P1") (pintype "power_in"))
      (node (ref "IC6") (pin "P3") (pinfunction "SD_GND9_P3") (pintype "power_in"))
      (node (ref "IC6") (pin "P5") (pinfunction "SD_GND10_P5") (pintype "power_in"))
      (node (ref "IC7") (pin "2") (pinfunction "GND_2") (pintype "passive"))
      (node (ref "R100") (pin "2") (pinfunction "2_2") (pintype "passive"))
      (node (ref "R101") (pin "2") (pinfunction "2_2") (pintype "passive"))
      (node (ref "R102") (pin "2") (pinfunction "2_2") (pintype "passive"))
      (node (ref "R103") (pin "2") (pinfunction "2_2") (pintype "passive"))
      (node (ref "R104") (pin "2") (pinfunction "2_2") (pintype "passive"))
      (node (ref "R105") (pin "2") (pinfunction "2_2") (pintype "passive"))
      (node (ref "R106") (pin "2") (pinfunction "2_2") (pintype "passive"))
      (node (ref "R107") (pin "2") (pinfunction "2_2") (pintype "passive"))
      (node (ref "R77") (pin "1") (pinfunction "1_1") (pintype "passive"))
      (node (ref "R85") (pin "2") (pinfunction "2_2") (pintype "passive"))
      (node (ref "R88") (pin "1") (pinfunction "1_1") (pintype "passive"))
      (node (ref "R99") (pin "2") (pinfunction "2_2") (pintype "passive"))
      (node (ref "X7") (pin "1") (pinfunction "1_1") (pintype "passive"))
      (node (ref "X7") (pin "12") (pinfunction "12_12") (pintype "passive"))
      (node (ref "X7") (pin "15") (pinfunction "15_15") (pintype "passive"))
      (node (ref "X7") (pin "4") (pinfunction "4_4") (pintype "passive"))
      (node (ref "X7") (pin "7") (pinfunction "7_7") (pintype "passive"))
      (node (ref "X7") (pin "9") (pinfunction "9_9") (pintype "passive"))
      (node (ref "X7") (pin "MP1") (pinfunction "MP1_MP1") (pintype "passive"))
      (node (ref "X7") (pin "MP2") (pinfunction "MP2_MP2") (pintype "passive"))
    )
    (net (code "75") (name "Net-(C126-Pad1)") (class "Default")
      (node (ref "C126") (pin "1") (pinfunction "1_1") (pintype "passive"))
      (node (ref "R82") (pin "1") (pinfunction "1_1") (pintype "passive"))
    )
    (net (code "76") (name "Net-(C132-Pad1)") (class "Default")
      (node (ref "C132") (pin "1") (pinfunction "1_1") (pintype "passive"))
      (node (ref "R86") (pin "1") (pinfunction "1_1") (pintype "passive"))
    )
    (net (code "77") (name "Net-(IC6A-CLKOUT)") (class "Default")
      (node (ref "IC6") (pin "N13") (pinfunction "CLKOUT_N13") (pintype "power_in"))
      (node (ref "R79") (pin "2") (pinfunction "2_2") (pintype "passive"))
    )
    (net (code "78") (name "Net-(IC6A-GPIO_19_{slash}ASLEEP)") (class "Default")
      (node (ref "IC6") (pin "R12") (pinfunction "GPIO_19_/ASLEEP_R12") (pintype "power_in"))
      (node (ref "R76") (pin "2") (pinfunction "2_2") (pintype "passive"))
    )
    (net (code "79") (name "Net-(IC6A-SCAN_MODE_B)") (class "Default")
      (node (ref "IC6") (pin "M13") (pinfunction "SCAN_MODE_B_M13") (pintype "power_in"))
      (node (ref "R87") (pin "1") (pinfunction "1_1") (pintype "passive"))
    )
    (net (code "80") (name "Net-(IC6A-SD1_IMP_CAL_RX)") (class "Default")
      (node (ref "IC6") (pin "K4") (pinfunction "SD1_IMP_CAL_RX_K4") (pintype "power_in"))
      (node (ref "R81") (pin "1") (pinfunction "1_1") (pintype "passive"))
    )
    (net (code "81") (name "Net-(IC6A-SD1_IMP_CAL_TX)") (class "Default")
      (node (ref "IC6") (pin "M4") (pinfunction "SD1_IMP_CAL_TX_M4") (pintype "power_in"))
      (node (ref "R80") (pin "1") (pinfunction "1_1") (pintype "passive"))
    )
    (net (code "82") (name "Net-(IC6B-IREF_TX)") (class "Default")
      (node (ref "IC6") (pin "E8") (pinfunction "IREF_TX_E8") (pintype "power_in"))
      (node (ref "R99") (pin "1") (pinfunction "1_1") (pintype "passive"))
    )
    (net (code "83") (name "Net-(IC7-D)") (class "Default")
      (node (ref "IC7") (pin "5") (pinfunction "D_5") (pintype "passive"))
      (node (ref "R78") (pin "1") (pinfunction "1_1") (pintype "passive"))
      (node (ref "R84") (pin "2") (pinfunction "2_2") (pintype "passive"))
      (node (ref "R85") (pin "1") (pinfunction "1_1") (pintype "passive"))
    )
    (net (code "84") (name "Net-(IC7-Y)") (class "Default")
      (node (ref "C126") (pin "2") (pinfunction "2_2") (pintype "passive"))
      (node (ref "IC7") (pin "4") (pinfunction "Y_4") (pintype "passive"))
      (node (ref "R77") (pin "2") (pinfunction "2_2") (pintype "passive"))
      (node (ref "R78") (pin "2") (pinfunction "2_2") (pintype "passive"))
    )
    (net (code "85") (name "Net-(IC7-Z)") (class "Default")
      (node (ref "C132") (pin "2") (pinfunction "2_2") (pintype "passive"))
      (node (ref "IC7") (pin "3") (pinfunction "Z_3") (pintype "passive"))
      (node (ref "R88") (pin "2") (pinfunction "2_2") (pintype "passive"))
    )
    (net (code "86") (name "Net-(J1-Pad6)") (class "Default")
      (node (ref "J1") (pin "6") (pinfunction "6_6") (pintype "passive"))
      (node (ref "R90") (pin "1") (pinfunction "1_1") (pintype "passive"))
    )
    (net (code "87") (name "Net-(R79-Pad1)") (class "Default")
      (node (ref "R79") (pin "1") (pinfunction "1_1") (pintype "passive"))
      (node (ref "TP1") (pin "1") (pintype "passive"))
    )
    (net (code "88") (name "VCC0P9") (class "Default")
      (node (ref "C139") (pin "2") (pinfunction "2_2") (pintype "passive"))
      (node (ref "C140") (pin "2") (pinfunction "2_2") (pintype "passive"))
      (node (ref "C141") (pin "2") (pinfunction "2_2") (pintype "passive"))
      (node (ref "C142") (pin "2") (pinfunction "2_2") (pintype "passive"))
      (node (ref "C143") (pin "2") (pinfunction "2_2") (pintype "passive"))
      (node (ref "C144") (pin "1") (pinfunction "1_1") (pintype "passive"))
      (node (ref "C148") (pin "1") (pinfunction "1_1") (pintype "passive"))
      (node (ref "C156") (pin "1") (pinfunction "1_1") (pintype "passive"))
      (node (ref "IC6") (pin "G10") (pinfunction "VDD2_G10") (pintype "power_in"))
      (node (ref "IC6") (pin "G6") (pinfunction "VDD1_G6") (pintype "power_in"))
      (node (ref "IC6") (pin "H11") (pinfunction "VDD6_H11") (pintype "power_in"))
      (node (ref "IC6") (pin "H5") (pinfunction "VDD3_H5") (pintype "power_in"))
      (node (ref "IC6") (pin "H7") (pinfunction "VDD4_H7") (pintype "power_in"))
      (node (ref "IC6") (pin "H9") (pinfunction "VDD5_H9") (pintype "power_in"))
      (node (ref "IC6") (pin "J10") (pinfunction "VDD8_J10") (pintype "power_in"))
      (node (ref "IC6") (pin "J6") (pinfunction "VDD7_J6") (pintype "power_in"))
    )
    (net (code "89") (name "VCC0P9_AFE_CVDD") (class "Default")
      (node (ref "C148") (pin "3") (pinfunction "3_3") (pintype "passive"))
      (node (ref "C152") (pin "2") (pinfunction "2_2") (pintype "passive"))
      (node (ref "C153") (pin "2") (pinfunction "2_2") (pintype "passive"))
      (node (ref "C154") (pin "2") (pinfunction "2_2") (pintype "passive"))
      (node (ref "C155") (pin "2") (pinfunction "2_2") (pintype "passive"))
      (node (ref "IC6") (pin "F11") (pinfunction "AFE_CVDD2_F11") (pintype "power_in"))
      (node (ref "IC6") (pin "F5") (pinfunction "AFE_CVDD1_F5") (pintype "power_in"))
    )
    (net (code "90") (name "VCC0P9_AFE_SVDD") (class "Default")
      (node (ref "C149") (pin "2") (pinfunction "2_2") (pintype "passive"))
      (node (ref "C150") (pin "1") (pinfunction "1_1") (pintype "passive"))
      (node (ref "C151") (pin "1") (pinfunction "1_1") (pintype "passive"))
      (node (ref "C156") (pin "3") (pinfunction "3_3") (pintype "passive"))
      (node (ref "C157") (pin "2") (pinfunction "2_2") (pintype "passive"))
      (node (ref "C158") (pin "2") (pinfunction "2_2") (pintype "passive"))
      (node (ref "C159") (pin "2") (pinfunction "2_2") (pintype "passive"))
      (node (ref "C160") (pin "2") (pinfunction "2_2") (pintype "passive"))
      (node (ref "C161") (pin "2") (pinfunction "2_2") (pintype "passive"))
      (node (ref "C162") (pin "2") (pinfunction "2_2") (pintype "passive"))
      (node (ref "IC6") (pin "D3") (pinfunction "VREF_RX_P_D3") (pintype "power_in"))
      (node (ref "IC6") (pin "E10") (pinfunction "AFE_SVDD2_E10") (pintype "power_in"))
      (node (ref "IC6") (pin "E6") (pinfunction "AFE_SVDD1_E6") (pintype "power_in"))
      (node (ref "IC6") (pin "F7") (pinfunction "AFE_SVDD3_F7") (pintype "power_in"))
      (node (ref "IC6") (pin "F9") (pinfunction "AFE_SVDD4_F9") (pintype "power_in"))
    )
    (net (code "91") (name "VCC0P9_SD_SVDD") (class "Default")
      (node (ref "C144") (pin "3") (pinfunction "3_3") (pintype "passive"))
      (node (ref "C145") (pin "2") (pinfunction "2_2") (pintype "passive"))
      (node (ref "C146") (pin "2") (pinfunction "2_2") (pintype "passive"))
      (node (ref "C147") (pin "2") (pinfunction "2_2") (pintype "passive"))
      (node (ref "IC6") (pin "K5") (pinfunction "SD_SVDD1_K5") (pintype "power_in"))
      (node (ref "IC6") (pin "K7") (pinfunction "SD_SVDD2_K7") (pintype "power_in"))
      (node (ref "R81") (pin "2") (pinfunction "2_2") (pintype "passive"))
    )
    (net (code "92") (name "VCC1P8") (class "Default")
      (node (ref "C130") (pin "2") (pinfunction "2_2") (pintype "passive"))
      (node (ref "C131") (pin "2") (pinfunction "2_2") (pintype "passive"))
      (node (ref "C135") (pin "1") (pinfunction "1_1") (pintype "passive"))
      (node (ref "IC6") (pin "K1") (pinfunction "TH_VDD_K1") (pintype "power_in"))
      (node (ref "IC6") (pin "K11") (pinfunction "OVDD2_K11") (pintype "power_in"))
      (node (ref "IC6") (pin "K9") (pinfunction "OVDD1_K9") (pintype "power_in"))
      (node (ref "IC6") (pin "L10") (pinfunction "OVDD3_L10") (pintype "power_in"))
      (node (ref "J1") (pin "4") (pinfunction "4_4") (pintype "passive"))
      (node (ref "R73") (pin "1") (pinfunction "1_1") (pintype "passive"))
      (node (ref "R74") (pin "1") (pinfunction "1_1") (pintype "passive"))
      (node (ref "R83") (pin "2") (pinfunction "2_2") (pintype "passive"))
      (node (ref "R87") (pin "2") (pinfunction "2_2") (pintype "passive"))
      (node (ref "R89") (pin "1") (pinfunction "1_1") (pintype "passive"))
    )
    (net (code "93") (name "VCC1P8_AFE_OTVDD") (class "Default")
      (node (ref "C135") (pin "3") (pinfunction "3_3") (pintype "passive"))
      (node (ref "C136") (pin "2") (pinfunction "2_2") (pintype "passive"))
      (node (ref "C137") (pin "2") (pinfunction "2_2") (pintype "passive"))
      (node (ref "C138") (pin "2") (pinfunction "2_2") (pintype "passive"))
      (node (ref "IC6") (pin "C8") (pinfunction "AFE_OTVDD_C8") (pintype "power_in"))
      (node (ref "IC6") (pin "D11") (pinfunction "AFE_OMVDD_D11") (pintype "power_in"))
    )
    (net (code "94") (name "VCC1P8_AVDD_PLAT") (class "Default")
      (node (ref "C127") (pin "2") (pinfunction "2_2") (pintype "passive"))
      (node (ref "C128") (pin "1") (pinfunction "1_1") (pintype "passive"))
      (node (ref "C129") (pin "1") (pinfunction "1_1") (pintype "passive"))
      (node (ref "IC6") (pin "H3") (pinfunction "AVDD_PLAT_H3") (pintype "power_in"))
      (node (ref "R83") (pin "1") (pinfunction "1_1") (pintype "passive"))
    )
    (net (code "95") (name "VCC1P35") (class "Default")
      (node (ref "C117") (pin "1") (pinfunction "1_1") (pintype "passive"))
      (node (ref "R75") (pin "2") (pinfunction "2_2") (pintype "passive"))
    )
    (net (code "96") (name "VCC1P35_AVDD_SD_PLL") (class "Default")
      (node (ref "C119") (pin "2") (pinfunction "2_2") (pintype "passive"))
      (node (ref "C120") (pin "2") (pinfunction "2_2") (pintype "passive"))
      (node (ref "C124") (pin "1") (pinfunction "1_1") (pintype "passive"))
      (node (ref "IC6") (pin "L3") (pinfunction "AVDD_SD_PLL_L3") (pintype "power_in"))
      (node (ref "R75") (pin "1") (pinfunction "1_1") (pintype "passive"))
    )
    (net (code "97") (name "VCC1P35_SD_XVDD") (class "Default")
      (node (ref "C117") (pin "3") (pinfunction "3_3") (pintype "passive"))
      (node (ref "C121") (pin "2") (pinfunction "2_2") (pintype "passive"))
      (node (ref "C122") (pin "2") (pinfunction "2_2") (pintype "passive"))
      (node (ref "C123") (pin "2") (pinfunction "2_2") (pintype "passive"))
      (node (ref "IC6") (pin "M5") (pinfunction "SD_XVDD1_M5") (pintype "power_in"))
      (node (ref "IC6") (pin "M6") (pinfunction "SD_XVDD2_M6") (pintype "power_in"))
      (node (ref "R80") (pin "2") (pinfunction "2_2") (pintype "passive"))
    )
    (net (code "98") (name "VCC3P3") (class "Default")
      (node (ref "X7") (pin "8") (pinfunction "8_8") (pintype "passive"))
    )
    (net (code "99") (name "VCC3P3_CLK") (class "Default")
      (node (ref "C133") (pin "2") (pinfunction "2_2") (pintype "passive"))
      (node (ref "C134") (pin "1") (pinfunction "1_1") (pintype "passive"))
      (node (ref "IC7") (pin "1") (pinfunction "VCC_1") (pintype "passive"))
    )
    (net (code "100") (name "VCC3P3_MPCIE") (class "Default")
      (node (ref "R72") (pin "1") (pinfunction "1_1") (pintype "passive"))
    )
    (net (code "101") (name "unconnected-(IC6B-LLCP_DOUT_N-PadG13)") (class "Default")
      (node (ref "IC6") (pin "G13") (pinfunction "LLCP_DOUT_N_G13") (pintype "power_in+no_connect"))
    )
    (net (code "102") (name "unconnected-(IC6B-LLCP_DOUT_P-PadF13)") (class "Default")
      (node (ref "IC6") (pin "F13") (pinfunction "LLCP_DOUT_P_F13") (pintype "power_in+no_connect"))
    )
    (net (code "103") (name "unconnected-(IC6B-LLCP_STOUT_N-PadF14)") (class "Default")
      (node (ref "IC6") (pin "F14") (pinfunction "LLCP_STOUT_N_F14") (pintype "power_in+no_connect"))
    )
    (net (code "104") (name "unconnected-(IC6B-LLCP_STOUT_P-PadF15)") (class "Default")
      (node (ref "IC6") (pin "F15") (pinfunction "LLCP_STOUT_P_F15") (pintype "power_in+no_connect"))
    )
    (net (code "105") (name "unconnected-(IC6B-TX_DET-PadD13)") (class "Default")
      (node (ref "IC6") (pin "D13") (pinfunction "TX_DET_D13") (pintype "power_in+no_connect"))
    )
  )
)
